# Triac3_ZeroCrossDetector_Module.net
KiCad netlist of a schematic drawn in EAGLE
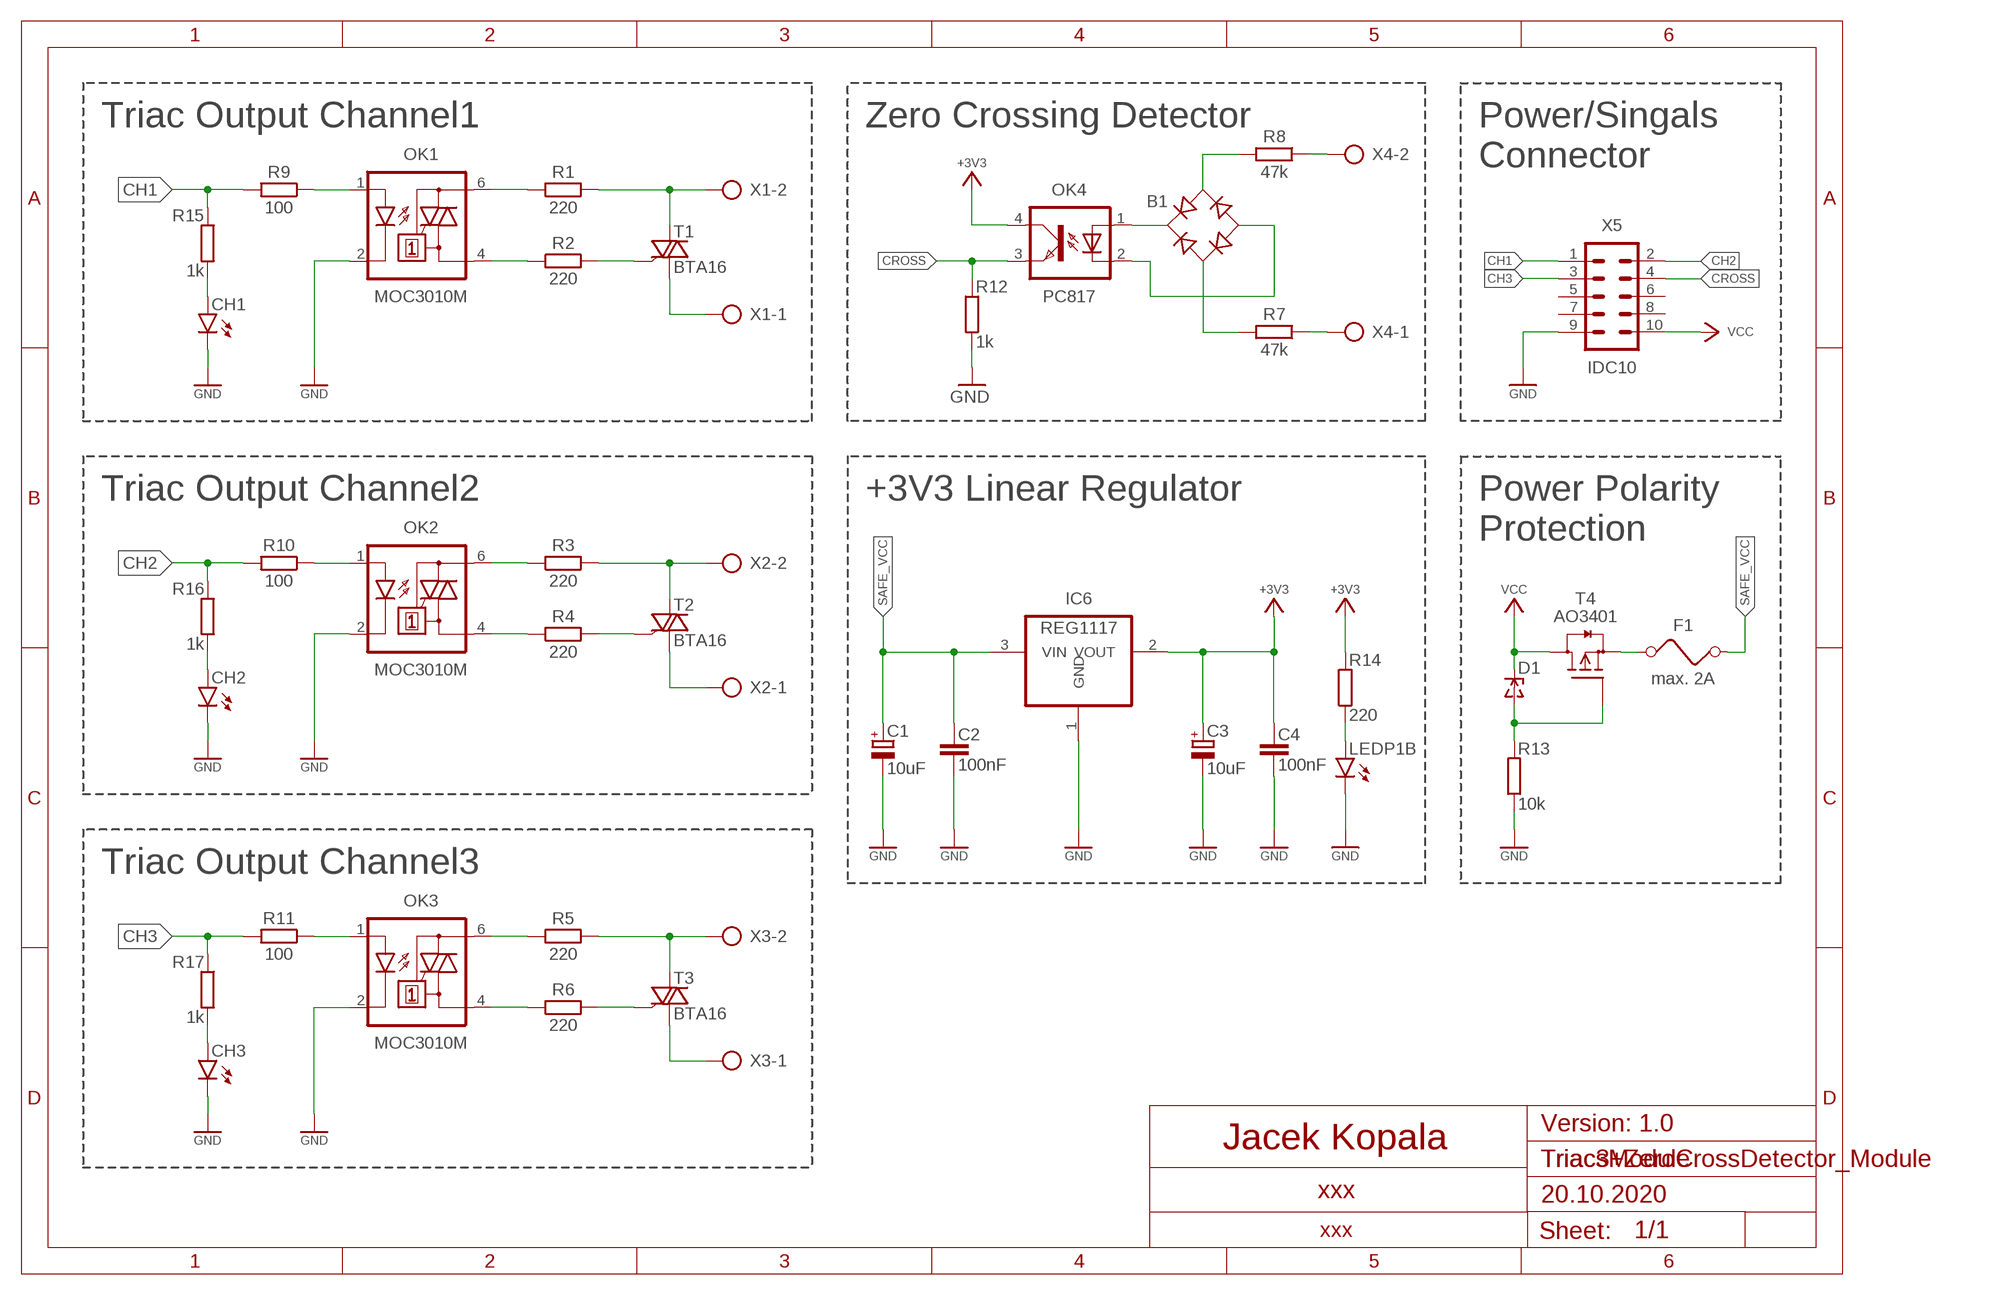
[diagram p0: schematic, sheet 1]

(export (version "E")
  (design (tool "Eeschema 10.0.6"))
  (components
    (comp (ref "B1")
      (value "RB1A")
      (footprint "eagle-import:RB1A")
      (libsource (lib "eagle-import") (part "RB1A"))
    )
    (comp (ref "C1")
      (value "10uF")
      (footprint "eagle-import:153CLV-0405")
      (libsource (lib "eagle-import") (part "CPOL-EU153CLV-0405"))
    )
    (comp (ref "C2")
      (value "100nF")
      (footprint "eagle-import:C0805")
      (fields (field (name "SPICEPREFIX") "C"))
      (libsource (lib "eagle-import") (part "C-EUC0805"))
    )
    (comp (ref "C3")
      (value "10uF")
      (footprint "eagle-import:153CLV-0405")
      (libsource (lib "eagle-import") (part "CPOL-EU153CLV-0405"))
    )
    (comp (ref "C4")
      (value "100nF")
      (footprint "eagle-import:C0805")
      (fields (field (name "SPICEPREFIX") "C"))
      (libsource (lib "eagle-import") (part "C-EUC0805"))
    )
    (comp (ref "CH1")
      (value "LEDCHIPLED_0805")
      (footprint "eagle-import:CHIPLED_0805")
      (libsource (lib "eagle-import") (part "LEDCHIPLED_0805"))
    )
    (comp (ref "CH2")
      (value "LEDCHIPLED_0805")
      (footprint "eagle-import:CHIPLED_0805")
      (libsource (lib "eagle-import") (part "LEDCHIPLED_0805"))
    )
    (comp (ref "CH3")
      (value "LEDCHIPLED_0805")
      (footprint "eagle-import:CHIPLED_0805")
      (libsource (lib "eagle-import") (part "LEDCHIPLED_0805"))
    )
    (comp (ref "D1")
      (value "ZENERSOD-323F")
      (footprint "eagle-import:SOD-323F")
      (libsource (lib "eagle-import") (part "ZENERSOD-323F"))
    )
    (comp (ref "F1")
      (value "max. 2A")
      (footprint "eagle-import:0805")
      (libsource (lib "eagle-import") (part "FUSEB"))
    )
    (comp (ref "IC6")
      (value "REG1117")
      (footprint "eagle-import:SOT223")
      (libsource (lib "eagle-import") (part "REG1117"))
    )
    (comp (ref "LEDP1")
      (value "LSG-T676")
      (footprint "eagle-import:WL-SFCW-0603")
      (libsource (lib "eagle-import") (part "LSG-T676"))
    )
    (comp (ref "OK1")
      (value "MOC3010M")
      (footprint "eagle-import:DIL06")
      (fields (field (name "MF") "FAIRCHILD SEMICONDUCTOR") (field (name "MPN") "MOC3010-M"))
      (libsource (lib "eagle-import") (part "MOC30M10"))
    )
    (comp (ref "OK2")
      (value "MOC3010M")
      (footprint "eagle-import:DIL06")
      (fields (field (name "MF") "FAIRCHILD SEMICONDUCTOR") (field (name "MPN") "MOC3010-M"))
      (libsource (lib "eagle-import") (part "MOC30M10"))
    )
    (comp (ref "OK3")
      (value "MOC3010M")
      (footprint "eagle-import:DIL06")
      (fields (field (name "MF") "FAIRCHILD SEMICONDUCTOR") (field (name "MPN") "MOC3010-M"))
      (libsource (lib "eagle-import") (part "MOC30M10"))
    )
    (comp (ref "OK4")
      (value "PC817")
      (footprint "eagle-import:DIL04")
      (libsource (lib "eagle-import") (part "PC817"))
    )
    (comp (ref "R1")
      (value "220")
      (footprint "eagle-import:0204_7")
      (libsource (lib "eagle-import") (part "R-EU_0204/7"))
    )
    (comp (ref "R2")
      (value "220")
      (footprint "eagle-import:0204_7")
      (libsource (lib "eagle-import") (part "R-EU_0204/7"))
    )
    (comp (ref "R3")
      (value "220")
      (footprint "eagle-import:0204_7")
      (libsource (lib "eagle-import") (part "R-EU_0204/7"))
    )
    (comp (ref "R4")
      (value "220")
      (footprint "eagle-import:0204_7")
      (libsource (lib "eagle-import") (part "R-EU_0204/7"))
    )
    (comp (ref "R5")
      (value "220")
      (footprint "eagle-import:0204_7")
      (libsource (lib "eagle-import") (part "R-EU_0204/7"))
    )
    (comp (ref "R6")
      (value "220")
      (footprint "eagle-import:0204_7")
      (libsource (lib "eagle-import") (part "R-EU_0204/7"))
    )
    (comp (ref "R7")
      (value "47k")
      (footprint "eagle-import:0207_10")
      (libsource (lib "eagle-import") (part "R-EU_0207/10"))
    )
    (comp (ref "R8")
      (value "47k")
      (footprint "eagle-import:0207_10")
      (libsource (lib "eagle-import") (part "R-EU_0207/10"))
    )
    (comp (ref "R9")
      (value "100")
      (footprint "eagle-import:R0805")
      (libsource (lib "eagle-import") (part "R-EU_R0805"))
    )
    (comp (ref "R10")
      (value "100")
      (footprint "eagle-import:R0805")
      (libsource (lib "eagle-import") (part "R-EU_R0805"))
    )
    (comp (ref "R11")
      (value "100")
      (footprint "eagle-import:R0805")
      (libsource (lib "eagle-import") (part "R-EU_R0805"))
    )
    (comp (ref "R12")
      (value "1k")
      (footprint "eagle-import:R0805")
      (libsource (lib "eagle-import") (part "R-EU_R0805"))
    )
    (comp (ref "R13")
      (value "10k")
      (footprint "eagle-import:R0805")
      (libsource (lib "eagle-import") (part "R-EU_R0805"))
    )
    (comp (ref "R14")
      (value "220")
      (footprint "eagle-import:R0805")
      (libsource (lib "eagle-import") (part "R-EU_R0805"))
    )
    (comp (ref "R15")
      (value "1k")
      (footprint "eagle-import:R0805")
      (libsource (lib "eagle-import") (part "R-EU_R0805"))
    )
    (comp (ref "R16")
      (value "1k")
      (footprint "eagle-import:R0805")
      (libsource (lib "eagle-import") (part "R-EU_R0805"))
    )
    (comp (ref "R17")
      (value "1k")
      (footprint "eagle-import:R0805")
      (libsource (lib "eagle-import") (part "R-EU_R0805"))
    )
    (comp (ref "T1")
      (value "BTA16")
      (footprint "eagle-import:TO220BV")
      (libsource (lib "eagle-import") (part "BTA16-V"))
    )
    (comp (ref "T2")
      (value "BTA16")
      (footprint "eagle-import:TO220BV")
      (libsource (lib "eagle-import") (part "BTA16-V"))
    )
    (comp (ref "T3")
      (value "BTA16")
      (footprint "eagle-import:TO220BV")
      (libsource (lib "eagle-import") (part "BTA16-V"))
    )
    (comp (ref "T4")
      (value "AO3401")
      (footprint "eagle-import:SOT23")
      (libsource (lib "eagle-import") (part "BSS84LT1"))
    )
    (comp (ref "X1")
      (value "TERMINAL7.5")
      (footprint "eagle-import:TERMINAL7.5")
      (libsource (lib "eagle-import") (part "TERMINAL7.5"))
    )
    (comp (ref "X2")
      (value "TERMINAL7.5")
      (footprint "eagle-import:TERMINAL7.5")
      (libsource (lib "eagle-import") (part "TERMINAL7.5"))
    )
    (comp (ref "X3")
      (value "TERMINAL7.5")
      (footprint "eagle-import:TERMINAL7.5")
      (libsource (lib "eagle-import") (part "TERMINAL7.5"))
    )
    (comp (ref "X4")
      (value "TERMINAL7.5")
      (footprint "eagle-import:TERMINAL7.5")
      (libsource (lib "eagle-import") (part "TERMINAL7.5"))
    )
    (comp (ref "X5")
      (value "IDC10")
      (footprint "eagle-import:ML10")
      (libsource (lib "eagle-import") (part "ML10"))
    )
  )
  (nets
    (net (code "1") (name "+3V3") (class "Default")
      (node (ref "C3") (pin "+") (pinfunction "+_+") (pintype "passive"))
      (node (ref "C4") (pin "1") (pinfunction "1_1") (pintype "passive"))
      (node (ref "IC6") (pin "2") (pinfunction "VOUT_2") (pintype "output"))
      (node (ref "OK4") (pin "4") (pinfunction "COL_4") (pintype "passive"))
      (node (ref "R14") (pin "2") (pinfunction "2_2") (pintype "passive"))
    )
    (net (code "2") (name "CH1") (class "Default")
      (node (ref "R15") (pin "1") (pinfunction "1_1") (pintype "passive"))
      (node (ref "R9") (pin "2") (pinfunction "2_2") (pintype "passive"))
      (node (ref "X5") (pin "1") (pinfunction "1_1") (pintype "passive"))
    )
    (net (code "3") (name "CH2") (class "Default")
      (node (ref "R10") (pin "2") (pinfunction "2_2") (pintype "passive"))
      (node (ref "R16") (pin "1") (pinfunction "1_1") (pintype "passive"))
      (node (ref "X5") (pin "2") (pinfunction "2_2") (pintype "passive"))
    )
    (net (code "4") (name "CH3") (class "Default")
      (node (ref "R11") (pin "2") (pinfunction "2_2") (pintype "passive"))
      (node (ref "R17") (pin "1") (pinfunction "1_1") (pintype "passive"))
      (node (ref "X5") (pin "3") (pinfunction "3_3") (pintype "passive"))
    )
    (net (code "5") (name "CROSS") (class "Default")
      (node (ref "OK4") (pin "3") (pinfunction "EMIT_3") (pintype "passive"))
      (node (ref "R12") (pin "2") (pinfunction "2_2") (pintype "passive"))
      (node (ref "X5") (pin "4") (pinfunction "4_4") (pintype "passive"))
    )
    (net (code "6") (name "GND") (class "Default")
      (node (ref "C1") (pin "-") (pinfunction "-_-") (pintype "passive"))
      (node (ref "C2") (pin "2") (pinfunction "2_2") (pintype "passive"))
      (node (ref "C3") (pin "-") (pinfunction "-_-") (pintype "passive"))
      (node (ref "C4") (pin "2") (pinfunction "2_2") (pintype "passive"))
      (node (ref "CH1") (pin "C") (pinfunction "C_C") (pintype "passive"))
      (node (ref "CH2") (pin "C") (pinfunction "C_C") (pintype "passive"))
      (node (ref "CH3") (pin "C") (pinfunction "C_C") (pintype "passive"))
      (node (ref "IC6") (pin "1") (pinfunction "GND_1") (pintype "power_in"))
      (node (ref "LEDP1") (pin "P$3") (pinfunction "C_P$3") (pintype "passive"))
      (node (ref "OK1") (pin "2") (pinfunction "C_2") (pintype "passive"))
      (node (ref "OK2") (pin "2") (pinfunction "C_2") (pintype "passive"))
      (node (ref "OK3") (pin "2") (pinfunction "C_2") (pintype "passive"))
      (node (ref "R12") (pin "1") (pinfunction "1_1") (pintype "passive"))
      (node (ref "R13") (pin "1") (pinfunction "1_1") (pintype "passive"))
      (node (ref "X5") (pin "9") (pinfunction "9_9") (pintype "passive"))
    )
    (net (code "7") (name "Net-(B1-PadAC1)") (class "Default")
      (node (ref "B1") (pin "AC1") (pinfunction "AC1_AC1") (pintype "passive"))
      (node (ref "R8") (pin "2") (pinfunction "2_2") (pintype "passive"))
    )
    (net (code "8") (name "Net-(B1-PadAC2)") (class "Default")
      (node (ref "B1") (pin "AC2") (pinfunction "AC2_AC2") (pintype "passive"))
      (node (ref "R7") (pin "2") (pinfunction "2_2") (pintype "passive"))
    )
    (net (code "9") (name "Net-(CH1-PadA)") (class "Default")
      (node (ref "CH1") (pin "A") (pinfunction "A_A") (pintype "passive"))
      (node (ref "R15") (pin "2") (pinfunction "2_2") (pintype "passive"))
    )
    (net (code "10") (name "Net-(CH2-PadA)") (class "Default")
      (node (ref "CH2") (pin "A") (pinfunction "A_A") (pintype "passive"))
      (node (ref "R16") (pin "2") (pinfunction "2_2") (pintype "passive"))
    )
    (net (code "11") (name "Net-(CH3-PadA)") (class "Default")
      (node (ref "CH3") (pin "A") (pinfunction "A_A") (pintype "passive"))
      (node (ref "R17") (pin "2") (pinfunction "2_2") (pintype "passive"))
    )
    (net (code "12") (name "Net-(LEDP1B-A)") (class "Default")
      (node (ref "LEDP1") (pin "P$4") (pinfunction "A_P$4") (pintype "passive"))
      (node (ref "R14") (pin "1") (pinfunction "1_1") (pintype "passive"))
    )
    (net (code "13") (name "Net-(OK1-A)") (class "Default")
      (node (ref "OK1") (pin "1") (pinfunction "A_1") (pintype "passive"))
      (node (ref "R9") (pin "1") (pinfunction "1_1") (pintype "passive"))
    )
    (net (code "14") (name "Net-(OK1-A1)") (class "Default")
      (node (ref "OK1") (pin "4") (pinfunction "A1_4") (pintype "passive"))
      (node (ref "R2") (pin "1") (pinfunction "1_1") (pintype "passive"))
    )
    (net (code "15") (name "Net-(OK1-A2)") (class "Default")
      (node (ref "OK1") (pin "6") (pinfunction "A2_6") (pintype "passive"))
      (node (ref "R1") (pin "1") (pinfunction "1_1") (pintype "passive"))
    )
    (net (code "16") (name "Net-(OK2-A)") (class "Default")
      (node (ref "OK2") (pin "1") (pinfunction "A_1") (pintype "passive"))
      (node (ref "R10") (pin "1") (pinfunction "1_1") (pintype "passive"))
    )
    (net (code "17") (name "Net-(OK2-A1)") (class "Default")
      (node (ref "OK2") (pin "4") (pinfunction "A1_4") (pintype "passive"))
      (node (ref "R4") (pin "1") (pinfunction "1_1") (pintype "passive"))
    )
    (net (code "18") (name "Net-(OK2-A2)") (class "Default")
      (node (ref "OK2") (pin "6") (pinfunction "A2_6") (pintype "passive"))
      (node (ref "R3") (pin "1") (pinfunction "1_1") (pintype "passive"))
    )
    (net (code "19") (name "Net-(OK3-A)") (class "Default")
      (node (ref "OK3") (pin "1") (pinfunction "A_1") (pintype "passive"))
      (node (ref "R11") (pin "1") (pinfunction "1_1") (pintype "passive"))
    )
    (net (code "20") (name "Net-(OK3-A1)") (class "Default")
      (node (ref "OK3") (pin "4") (pinfunction "A1_4") (pintype "passive"))
      (node (ref "R6") (pin "1") (pinfunction "1_1") (pintype "passive"))
    )
    (net (code "21") (name "Net-(OK3-A2)") (class "Default")
      (node (ref "OK3") (pin "6") (pinfunction "A2_6") (pintype "passive"))
      (node (ref "R5") (pin "1") (pinfunction "1_1") (pintype "passive"))
    )
    (net (code "22") (name "Net-(OK4-A)") (class "Default")
      (node (ref "B1") (pin "+") (pinfunction "+_+") (pintype "passive"))
      (node (ref "OK4") (pin "1") (pinfunction "A_1") (pintype "passive"))
    )
    (net (code "23") (name "Net-(OK4-C)") (class "Default")
      (node (ref "B1") (pin "-") (pinfunction "-_-") (pintype "passive"))
      (node (ref "OK4") (pin "2") (pinfunction "C_2") (pintype "passive"))
    )
    (net (code "24") (name "Net-(R2-Pad2)") (class "Default")
      (node (ref "R2") (pin "2") (pinfunction "2_2") (pintype "passive"))
      (node (ref "T1") (pin "G") (pinfunction "G_G") (pintype "passive"))
    )
    (net (code "25") (name "Net-(R4-Pad2)") (class "Default")
      (node (ref "R4") (pin "2") (pinfunction "2_2") (pintype "passive"))
      (node (ref "T2") (pin "G") (pinfunction "G_G") (pintype "passive"))
    )
    (net (code "26") (name "Net-(R6-Pad2)") (class "Default")
      (node (ref "R6") (pin "2") (pinfunction "2_2") (pintype "passive"))
      (node (ref "T3") (pin "G") (pinfunction "G_G") (pintype "passive"))
    )
    (net (code "27") (name "Net-(T1-A1)") (class "Default")
      (node (ref "T1") (pin "T1") (pinfunction "A1_T1") (pintype "passive"))
      (node (ref "X1") (pin "1") (pinfunction "KL_1") (pintype "passive"))
    )
    (net (code "28") (name "Net-(T1-A2)") (class "Default")
      (node (ref "R1") (pin "2") (pinfunction "2_2") (pintype "passive"))
      (node (ref "T1") (pin "T2") (pinfunction "A2_T2") (pintype "passive"))
      (node (ref "X1") (pin "2") (pinfunction "KL_2") (pintype "passive"))
    )
    (net (code "29") (name "Net-(T2-A1)") (class "Default")
      (node (ref "T2") (pin "T1") (pinfunction "A1_T1") (pintype "passive"))
      (node (ref "X2") (pin "1") (pinfunction "KL_1") (pintype "passive"))
    )
    (net (code "30") (name "Net-(T2-A2)") (class "Default")
      (node (ref "R3") (pin "2") (pinfunction "2_2") (pintype "passive"))
      (node (ref "T2") (pin "T2") (pinfunction "A2_T2") (pintype "passive"))
      (node (ref "X2") (pin "2") (pinfunction "KL_2") (pintype "passive"))
    )
    (net (code "31") (name "Net-(T3-A1)") (class "Default")
      (node (ref "T3") (pin "T1") (pinfunction "A1_T1") (pintype "passive"))
      (node (ref "X3") (pin "1") (pinfunction "KL_1") (pintype "passive"))
    )
    (net (code "32") (name "Net-(T3-A2)") (class "Default")
      (node (ref "R5") (pin "2") (pinfunction "2_2") (pintype "passive"))
      (node (ref "T3") (pin "T2") (pinfunction "A2_T2") (pintype "passive"))
      (node (ref "X3") (pin "2") (pinfunction "KL_2") (pintype "passive"))
    )
    (net (code "33") (name "Net-(T4-G)") (class "Default")
      (node (ref "D1") (pin "A") (pinfunction "A_A") (pintype "passive"))
      (node (ref "R13") (pin "2") (pinfunction "2_2") (pintype "passive"))
      (node (ref "T4") (pin "1") (pinfunction "G_1") (pintype "passive"))
    )
    (net (code "34") (name "Net-(T4-S)") (class "Default")
      (node (ref "F1") (pin "1") (pinfunction "1_1") (pintype "passive"))
      (node (ref "T4") (pin "2") (pinfunction "S_2") (pintype "passive"))
    )
    (net (code "35") (name "Net-(X4A-KL)") (class "Default")
      (node (ref "R7") (pin "1") (pinfunction "1_1") (pintype "passive"))
      (node (ref "X4") (pin "1") (pinfunction "KL_1") (pintype "passive"))
    )
    (net (code "36") (name "Net-(X4B-KL)") (class "Default")
      (node (ref "R8") (pin "1") (pinfunction "1_1") (pintype "passive"))
      (node (ref "X4") (pin "2") (pinfunction "KL_2") (pintype "passive"))
    )
    (net (code "37") (name "SAFE_VCC") (class "Default")
      (node (ref "C1") (pin "+") (pinfunction "+_+") (pintype "passive"))
      (node (ref "C2") (pin "1") (pinfunction "1_1") (pintype "passive"))
      (node (ref "F1") (pin "2") (pinfunction "2_2") (pintype "passive"))
      (node (ref "IC6") (pin "3") (pinfunction "VIN_3") (pintype "input"))
    )
    (net (code "38") (name "VCC") (class "Default")
      (node (ref "D1") (pin "C") (pinfunction "C_C") (pintype "passive"))
      (node (ref "T4") (pin "3") (pinfunction "D_3") (pintype "passive"))
      (node (ref "X5") (pin "10") (pinfunction "10_10") (pintype "passive"))
    )
    (net (code "39") (name "unconnected-(X5-Pad5)") (class "Default")
      (node (ref "X5") (pin "5") (pinfunction "5_5") (pintype "passive"))
    )
    (net (code "40") (name "unconnected-(X5-Pad6)") (class "Default")
      (node (ref "X5") (pin "6") (pinfunction "6_6") (pintype "passive"))
    )
    (net (code "41") (name "unconnected-(X5-Pad7)") (class "Default")
      (node (ref "X5") (pin "7") (pinfunction "7_7") (pintype "passive"))
    )
    (net (code "42") (name "unconnected-(X5-Pad8)") (class "Default")
      (node (ref "X5") (pin "8") (pinfunction "8_8") (pintype "passive"))
    )
  )
)
